# TDC.net
KiCad netlist of a schematic drawn in Altium Designer
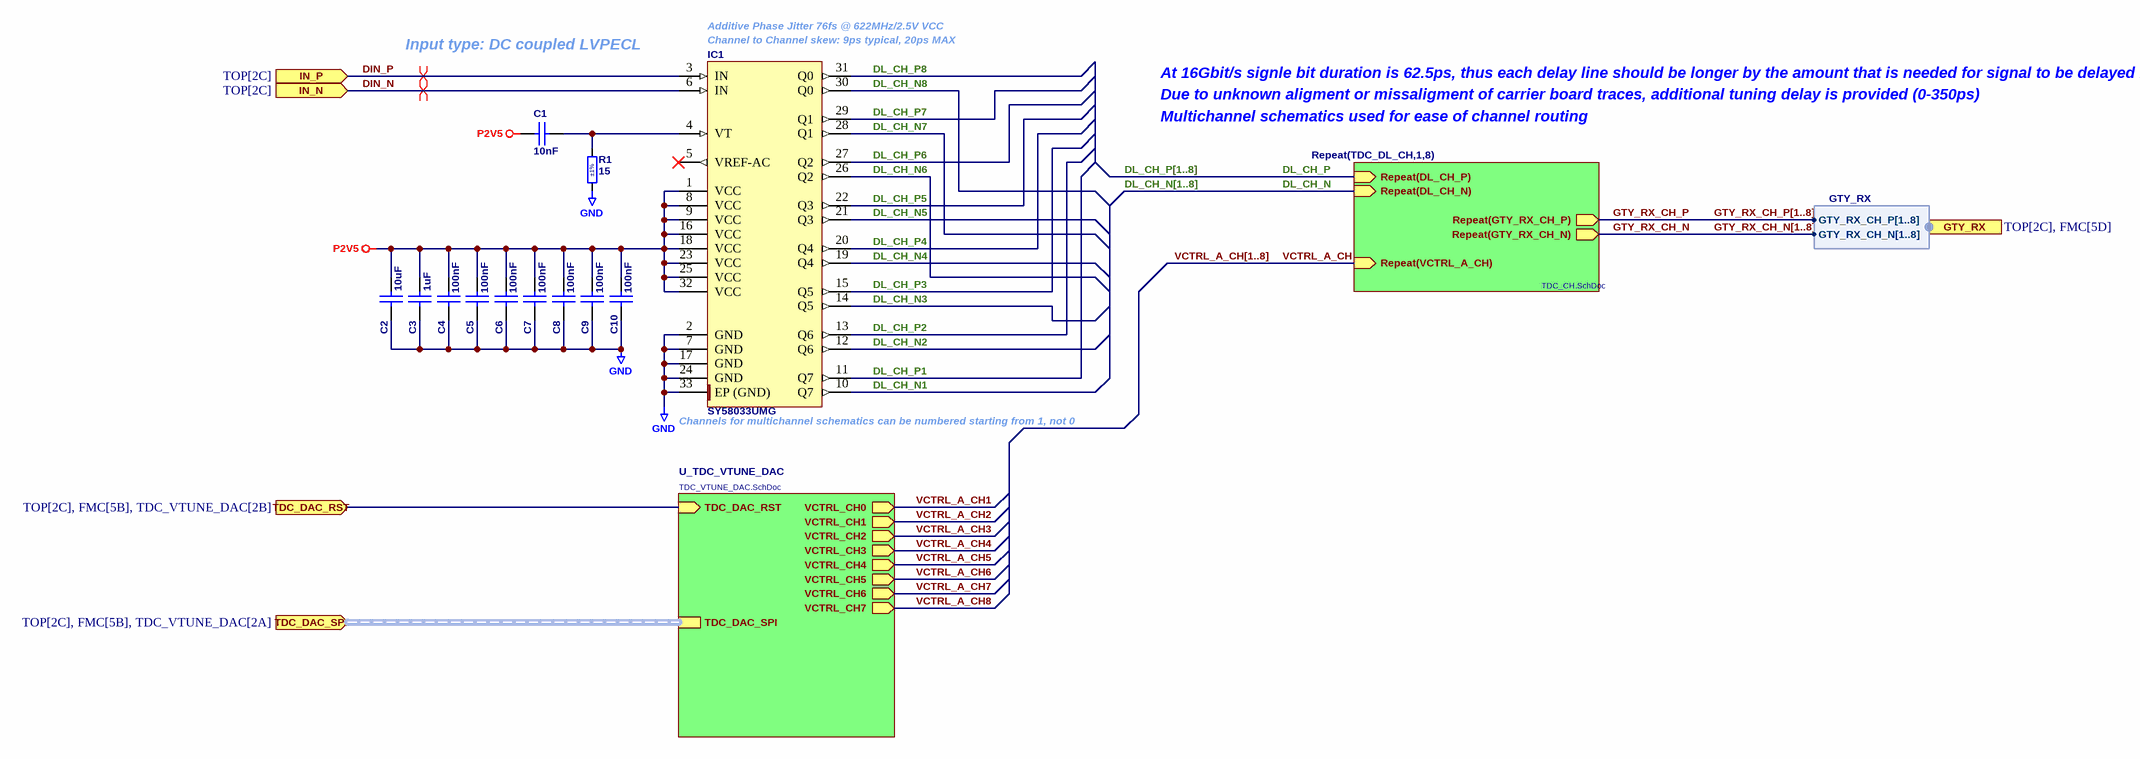
[diagram p0: TDC.SchDoc]

(export (version "E")
  (design (tool "Eeschema 10.0.6"))
  (components
    (comp (ref "C1")
      (value "10nF")
      (footprint "CAPC1005X55N")
      (description "Non-polarised capacitor")
      (fields
        (field (name "PART NUMBER") "CC0402_10NF_16V_10%_X7R")
        (field (name "VOLTAGE") "16V")
        (field (name "AUTHOR") "CERN DEM JLC")
      )
      (libsource (lib "Capacitors") (part "Capacitor - non polarized"))
    )
    (comp (ref "C2")
      (value "10uF")
      (footprint "CAPC1608X90N")
      (description "Non-polarised capacitor")
      (fields
        (field (name "PART NUMBER") "CC0603_10UF_16V_10%_X5R_MURATA_GRT188R61C106KE13")
        (field (name "VOLTAGE") "16V")
        (field (name "AUTHOR") "CERN DEM HF")
      )
      (libsource (lib "Capacitors") (part "Capacitor - non polarized"))
    )
    (comp (ref "C3")
      (value "1uF")
      (footprint "CAPC1005X55N")
      (description "Non-polarised capacitor")
      (fields
        (field (name "PART NUMBER") "CC0402_1UF_16V_10%_X5R")
        (field (name "VOLTAGE") "16V")
        (field (name "AUTHOR") "CERN DEM JLC")
      )
      (libsource (lib "Capacitors") (part "Capacitor - non polarized"))
    )
    (comp (ref "C4")
      (value "100nF")
      (footprint "CAPC1005X55N")
      (description "Non-polarised capacitor")
      (fields
        (field (name "PART NUMBER") "CC0402_100NF_16V_10%_X5R")
        (field (name "VOLTAGE") "16V")
        (field (name "AUTHOR") "CERN DEM JLC")
      )
      (libsource (lib "Capacitors") (part "Capacitor - non polarized"))
    )
    (comp (ref "C5")
      (value "100nF")
      (footprint "CAPC1005X55N")
      (description "Non-polarised capacitor")
      (fields
        (field (name "PART NUMBER") "CC0402_100NF_16V_10%_X5R")
        (field (name "VOLTAGE") "16V")
        (field (name "AUTHOR") "CERN DEM JLC")
      )
      (libsource (lib "Capacitors") (part "Capacitor - non polarized"))
    )
    (comp (ref "C6")
      (value "100nF")
      (footprint "CAPC1005X55N")
      (description "Non-polarised capacitor")
      (fields
        (field (name "PART NUMBER") "CC0402_100NF_16V_10%_X5R")
        (field (name "VOLTAGE") "16V")
        (field (name "AUTHOR") "CERN DEM JLC")
      )
      (libsource (lib "Capacitors") (part "Capacitor - non polarized"))
    )
    (comp (ref "C7")
      (value "100nF")
      (footprint "CAPC1005X55N")
      (description "Non-polarised capacitor")
      (fields
        (field (name "PART NUMBER") "CC0402_100NF_16V_10%_X5R")
        (field (name "VOLTAGE") "16V")
        (field (name "AUTHOR") "CERN DEM JLC")
      )
      (libsource (lib "Capacitors") (part "Capacitor - non polarized"))
    )
    (comp (ref "C8")
      (value "100nF")
      (footprint "CAPC1005X55N")
      (description "Non-polarised capacitor")
      (fields
        (field (name "PART NUMBER") "CC0402_100NF_16V_10%_X5R")
        (field (name "VOLTAGE") "16V")
        (field (name "AUTHOR") "CERN DEM JLC")
      )
      (libsource (lib "Capacitors") (part "Capacitor - non polarized"))
    )
    (comp (ref "C9")
      (value "100nF")
      (footprint "CAPC1005X55N")
      (description "Non-polarised capacitor")
      (fields
        (field (name "PART NUMBER") "CC0402_100NF_16V_10%_X5R")
        (field (name "VOLTAGE") "16V")
        (field (name "AUTHOR") "CERN DEM JLC")
      )
      (libsource (lib "Capacitors") (part "Capacitor - non polarized"))
    )
    (comp (ref "C10")
      (value "100nF")
      (footprint "CAPC1005X55N")
      (description "Non-polarised capacitor")
      (fields
        (field (name "PART NUMBER") "CC0402_100NF_16V_10%_X5R")
        (field (name "VOLTAGE") "16V")
        (field (name "AUTHOR") "CERN DEM JLC")
      )
      (libsource (lib "Capacitors") (part "Capacitor - non polarized"))
    )
    (comp (ref "IC1")
      (value "SY58033UMG")
      (footprint "QFN50P500X500X90_HS-33N")
      (description "ULTRA-PRECISION 1:8 BUFFER WITH 400mV LVPECL OUTPUTS AND INTERNAL TERMINATION")
      (libsource (lib "SPREAD_BUFFER") (part "SY58033U"))
    )
    (comp (ref "R1")
      (value "15")
      (footprint "RESC1005X40N")
      (description "Resistor - 1%")
      (fields
        (field (name "TOLERANCE") "±1%")
        (field (name "PART NUMBER") "R0402_15R_1%_0.0625W_100PPM")
        (field (name "POWER") "0.0625W")
        (field (name "AUTHOR") "CERN DEM JLC")
      )
      (libsource (lib "Resistors") (part "Resistor - 1%"))
    )
  )
  (nets
    (net (code "11") (name "/DIN_N") (class "Default")
      (node (ref "IC1") (pin "6") (pinfunction "IN_6") (pintype "input"))
    )
    (net (code "12") (name "/DIN_P") (class "Default")
      (node (ref "IC1") (pin "3") (pinfunction "IN_3") (pintype "input"))
    )
    (net (code "14") (name "/DL_CH_N1") (class "Default")
      (node (ref "IC1") (pin "10") (pinfunction "Q7_10") (pintype "output"))
    )
    (net (code "15") (name "/DL_CH_N2") (class "Default")
      (node (ref "IC1") (pin "12") (pinfunction "Q6_12") (pintype "output"))
    )
    (net (code "16") (name "/DL_CH_N3") (class "Default")
      (node (ref "IC1") (pin "14") (pinfunction "Q5_14") (pintype "output"))
    )
    (net (code "17") (name "/DL_CH_N4") (class "Default")
      (node (ref "IC1") (pin "19") (pinfunction "Q4_19") (pintype "output"))
    )
    (net (code "18") (name "/DL_CH_N5") (class "Default")
      (node (ref "IC1") (pin "21") (pinfunction "Q3_21") (pintype "output"))
    )
    (net (code "19") (name "/DL_CH_N6") (class "Default")
      (node (ref "IC1") (pin "26") (pinfunction "Q2_26") (pintype "output"))
    )
    (net (code "20") (name "/DL_CH_N7") (class "Default")
      (node (ref "IC1") (pin "28") (pinfunction "Q1_28") (pintype "output"))
    )
    (net (code "21") (name "/DL_CH_N8") (class "Default")
      (node (ref "IC1") (pin "30") (pinfunction "Q0_30") (pintype "output"))
    )
    (net (code "24") (name "/DL_CH_P1") (class "Default")
      (node (ref "IC1") (pin "11") (pinfunction "Q7_11") (pintype "output"))
    )
    (net (code "25") (name "/DL_CH_P2") (class "Default")
      (node (ref "IC1") (pin "13") (pinfunction "Q6_13") (pintype "output"))
    )
    (net (code "26") (name "/DL_CH_P3") (class "Default")
      (node (ref "IC1") (pin "15") (pinfunction "Q5_15") (pintype "output"))
    )
    (net (code "27") (name "/DL_CH_P4") (class "Default")
      (node (ref "IC1") (pin "20") (pinfunction "Q4_20") (pintype "output"))
    )
    (net (code "28") (name "/DL_CH_P5") (class "Default")
      (node (ref "IC1") (pin "22") (pinfunction "Q3_22") (pintype "output"))
    )
    (net (code "29") (name "/DL_CH_P6") (class "Default")
      (node (ref "IC1") (pin "27") (pinfunction "Q2_27") (pintype "output"))
    )
    (net (code "30") (name "/DL_CH_P7") (class "Default")
      (node (ref "IC1") (pin "29") (pinfunction "Q1_29") (pintype "output"))
    )
    (net (code "31") (name "/DL_CH_P8") (class "Default")
      (node (ref "IC1") (pin "31") (pinfunction "Q0_31") (pintype "output"))
    )
    (net (code "49") (name "GND") (class "Default")
      (node (ref "C10") (pin "1") (pinfunction "1_1") (pintype "passive"))
      (node (ref "C2") (pin "1") (pinfunction "1_1") (pintype "passive"))
      (node (ref "C3") (pin "1") (pinfunction "1_1") (pintype "passive"))
      (node (ref "C4") (pin "1") (pinfunction "1_1") (pintype "passive"))
      (node (ref "C5") (pin "1") (pinfunction "1_1") (pintype "passive"))
      (node (ref "C6") (pin "1") (pinfunction "1_1") (pintype "passive"))
      (node (ref "C7") (pin "1") (pinfunction "1_1") (pintype "passive"))
      (node (ref "C8") (pin "1") (pinfunction "1_1") (pintype "passive"))
      (node (ref "C9") (pin "1") (pinfunction "1_1") (pintype "passive"))
      (node (ref "IC1") (pin "17") (pinfunction "GND_17") (pintype "power_in"))
      (node (ref "IC1") (pin "2") (pinfunction "GND_2") (pintype "power_in"))
      (node (ref "IC1") (pin "24") (pinfunction "GND_24") (pintype "power_in"))
      (node (ref "IC1") (pin "33") (pinfunction "EP_(GND)_33") (pintype "power_in"))
      (node (ref "IC1") (pin "7") (pinfunction "GND_7") (pintype "power_in"))
      (node (ref "R1") (pin "1") (pinfunction "1_1") (pintype "passive"))
    )
    (net (code "50") (name "Net-(IC1-VT)") (class "Default")
      (node (ref "C1") (pin "1") (pinfunction "1_1") (pintype "passive"))
      (node (ref "IC1") (pin "4") (pinfunction "VT_4") (pintype "input"))
      (node (ref "R1") (pin "2") (pinfunction "2_2") (pintype "passive"))
    )
    (net (code "51") (name "P2V5") (class "Default")
      (node (ref "C1") (pin "2") (pinfunction "2_2") (pintype "passive"))
      (node (ref "C10") (pin "2") (pinfunction "2_2") (pintype "passive"))
      (node (ref "C2") (pin "2") (pinfunction "2_2") (pintype "passive"))
      (node (ref "C3") (pin "2") (pinfunction "2_2") (pintype "passive"))
      (node (ref "C4") (pin "2") (pinfunction "2_2") (pintype "passive"))
      (node (ref "C5") (pin "2") (pinfunction "2_2") (pintype "passive"))
      (node (ref "C6") (pin "2") (pinfunction "2_2") (pintype "passive"))
      (node (ref "C7") (pin "2") (pinfunction "2_2") (pintype "passive"))
      (node (ref "C8") (pin "2") (pinfunction "2_2") (pintype "passive"))
      (node (ref "C9") (pin "2") (pinfunction "2_2") (pintype "passive"))
      (node (ref "IC1") (pin "1") (pinfunction "VCC_1") (pintype "power_in"))
      (node (ref "IC1") (pin "16") (pinfunction "VCC_16") (pintype "power_in"))
      (node (ref "IC1") (pin "18") (pinfunction "VCC_18") (pintype "power_in"))
      (node (ref "IC1") (pin "23") (pinfunction "VCC_23") (pintype "power_in"))
      (node (ref "IC1") (pin "25") (pinfunction "VCC_25") (pintype "power_in"))
      (node (ref "IC1") (pin "32") (pinfunction "VCC_32") (pintype "power_in"))
      (node (ref "IC1") (pin "8") (pinfunction "VCC_8") (pintype "power_in"))
      (node (ref "IC1") (pin "9") (pinfunction "VCC_9") (pintype "power_in"))
    )
    (net (code "52") (name "unconnected-(IC1-VREF-AC-Pad5)") (class "Default")
      (node (ref "IC1") (pin "5") (pinfunction "VREF-AC_5") (pintype "output+no_connect"))
    )
  )
)
